# LED_backlight.net
KiCad netlist of a schematic drawn in Altium Designer
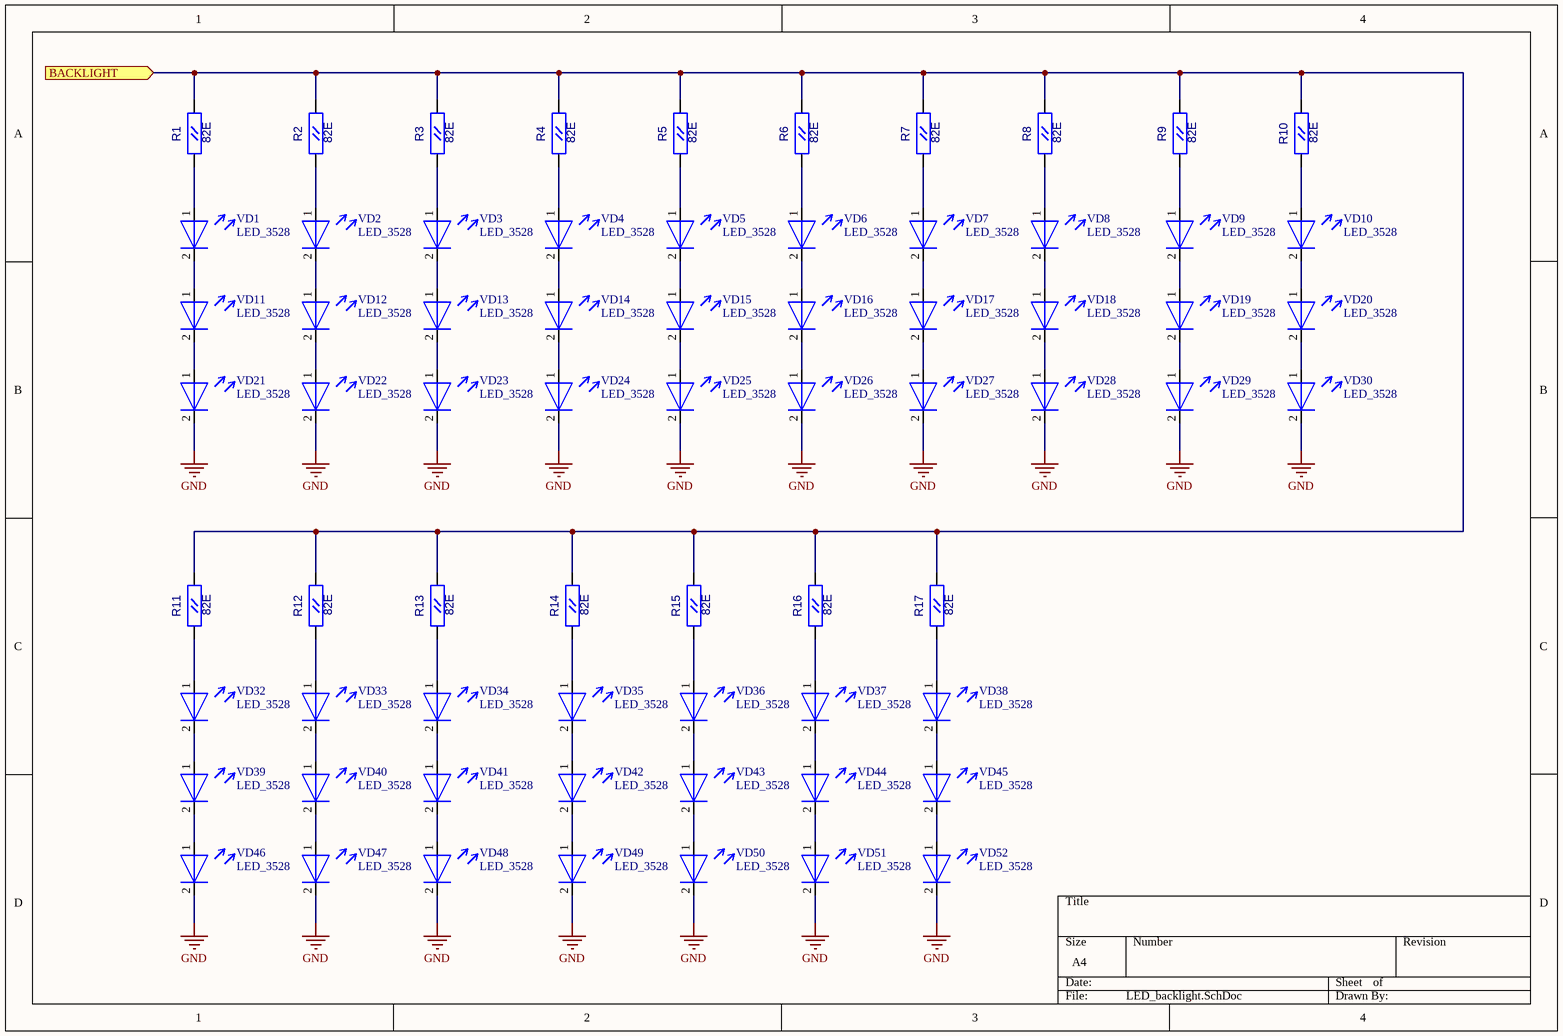
[diagram p0: LED_backlight.SchDoc]

(export (version "E")
  (design (tool "Eeschema 10.0.6"))
  (components
    (comp (ref "R1")
      (value "82E")
      (footprint "RC0805")
      (description "RC0805")
      (libsource (lib "gprs_modem_2") (part "RC0805"))
    )
    (comp (ref "R2")
      (value "82E")
      (footprint "RC0805")
      (description "RC0805")
      (libsource (lib "gprs_modem_2") (part "RC0805"))
    )
    (comp (ref "R3")
      (value "82E")
      (footprint "RC0805")
      (description "RC0805")
      (libsource (lib "gprs_modem_2") (part "RC0805"))
    )
    (comp (ref "R4")
      (value "82E")
      (footprint "RC0805")
      (description "RC0805")
      (libsource (lib "gprs_modem_2") (part "RC0805"))
    )
    (comp (ref "R5")
      (value "82E")
      (footprint "RC0805")
      (description "RC0805")
      (libsource (lib "gprs_modem_2") (part "RC0805"))
    )
    (comp (ref "R6")
      (value "82E")
      (footprint "RC0805")
      (description "RC0805")
      (libsource (lib "gprs_modem_2") (part "RC0805"))
    )
    (comp (ref "R7")
      (value "82E")
      (footprint "RC0805")
      (description "RC0805")
      (libsource (lib "gprs_modem_2") (part "RC0805"))
    )
    (comp (ref "R8")
      (value "82E")
      (footprint "RC0805")
      (description "RC0805")
      (libsource (lib "gprs_modem_2") (part "RC0805"))
    )
    (comp (ref "R9")
      (value "82E")
      (footprint "RC0805")
      (description "RC0805")
      (libsource (lib "gprs_modem_2") (part "RC0805"))
    )
    (comp (ref "R10")
      (value "82E")
      (footprint "RC0805")
      (description "RC0805")
      (libsource (lib "gprs_modem_2") (part "RC0805"))
    )
    (comp (ref "R11")
      (value "82E")
      (footprint "RC0805")
      (description "RC0805")
      (libsource (lib "gprs_modem_2") (part "RC0805"))
    )
    (comp (ref "R12")
      (value "82E")
      (footprint "RC0805")
      (description "RC0805")
      (libsource (lib "gprs_modem_2") (part "RC0805"))
    )
    (comp (ref "R13")
      (value "82E")
      (footprint "RC0805")
      (description "RC0805")
      (libsource (lib "gprs_modem_2") (part "RC0805"))
    )
    (comp (ref "R14")
      (value "82E")
      (footprint "RC0805")
      (description "RC0805")
      (libsource (lib "gprs_modem_2") (part "RC0805"))
    )
    (comp (ref "R15")
      (value "82E")
      (footprint "RC0805")
      (description "RC0805")
      (libsource (lib "gprs_modem_2") (part "RC0805"))
    )
    (comp (ref "R16")
      (value "82E")
      (footprint "RC0805")
      (description "RC0805")
      (libsource (lib "gprs_modem_2") (part "RC0805"))
    )
    (comp (ref "R17")
      (value "82E")
      (footprint "RC0805")
      (description "RC0805")
      (libsource (lib "gprs_modem_2") (part "RC0805"))
    )
    (comp (ref "VD1") (value "LED_3528") (footprint "3528LED") (libsource (lib "VHF") (part "3528LED")))
    (comp (ref "VD2") (value "LED_3528") (footprint "3528LED") (libsource (lib "VHF") (part "3528LED")))
    (comp (ref "VD3") (value "LED_3528") (footprint "3528LED") (libsource (lib "VHF") (part "3528LED")))
    (comp (ref "VD4") (value "LED_3528") (footprint "3528LED") (libsource (lib "VHF") (part "3528LED")))
    (comp (ref "VD5") (value "LED_3528") (footprint "3528LED") (libsource (lib "VHF") (part "3528LED")))
    (comp (ref "VD6") (value "LED_3528") (footprint "3528LED") (libsource (lib "VHF") (part "3528LED")))
    (comp (ref "VD7") (value "LED_3528") (footprint "3528LED") (libsource (lib "VHF") (part "3528LED")))
    (comp (ref "VD8") (value "LED_3528") (footprint "3528LED") (libsource (lib "VHF") (part "3528LED")))
    (comp (ref "VD9") (value "LED_3528") (footprint "3528LED") (libsource (lib "VHF") (part "3528LED")))
    (comp (ref "VD10") (value "LED_3528") (footprint "3528LED") (libsource (lib "VHF") (part "3528LED")))
    (comp (ref "VD11") (value "LED_3528") (footprint "3528LED") (libsource (lib "VHF") (part "3528LED")))
    (comp (ref "VD12") (value "LED_3528") (footprint "3528LED") (libsource (lib "VHF") (part "3528LED")))
    (comp (ref "VD13") (value "LED_3528") (footprint "3528LED") (libsource (lib "VHF") (part "3528LED")))
    (comp (ref "VD14") (value "LED_3528") (footprint "3528LED") (libsource (lib "VHF") (part "3528LED")))
    (comp (ref "VD15") (value "LED_3528") (footprint "3528LED") (libsource (lib "VHF") (part "3528LED")))
    (comp (ref "VD16") (value "LED_3528") (footprint "3528LED") (libsource (lib "VHF") (part "3528LED")))
    (comp (ref "VD17") (value "LED_3528") (footprint "3528LED") (libsource (lib "VHF") (part "3528LED")))
    (comp (ref "VD18") (value "LED_3528") (footprint "3528LED") (libsource (lib "VHF") (part "3528LED")))
    (comp (ref "VD19") (value "LED_3528") (footprint "3528LED") (libsource (lib "VHF") (part "3528LED")))
    (comp (ref "VD20") (value "LED_3528") (footprint "3528LED") (libsource (lib "VHF") (part "3528LED")))
    (comp (ref "VD21") (value "LED_3528") (footprint "3528LED") (libsource (lib "VHF") (part "3528LED")))
    (comp (ref "VD22") (value "LED_3528") (footprint "3528LED") (libsource (lib "VHF") (part "3528LED")))
    (comp (ref "VD23") (value "LED_3528") (footprint "3528LED") (libsource (lib "VHF") (part "3528LED")))
    (comp (ref "VD24") (value "LED_3528") (footprint "3528LED") (libsource (lib "VHF") (part "3528LED")))
    (comp (ref "VD25") (value "LED_3528") (footprint "3528LED") (libsource (lib "VHF") (part "3528LED")))
    (comp (ref "VD26") (value "LED_3528") (footprint "3528LED") (libsource (lib "VHF") (part "3528LED")))
    (comp (ref "VD27") (value "LED_3528") (footprint "3528LED") (libsource (lib "VHF") (part "3528LED")))
    (comp (ref "VD28") (value "LED_3528") (footprint "3528LED") (libsource (lib "VHF") (part "3528LED")))
    (comp (ref "VD29") (value "LED_3528") (footprint "3528LED") (libsource (lib "VHF") (part "3528LED")))
    (comp (ref "VD30") (value "LED_3528") (footprint "3528LED") (libsource (lib "VHF") (part "3528LED")))
    (comp (ref "VD32") (value "LED_3528") (footprint "3528LED") (libsource (lib "VHF") (part "3528LED")))
    (comp (ref "VD33") (value "LED_3528") (footprint "3528LED") (libsource (lib "VHF") (part "3528LED")))
    (comp (ref "VD34") (value "LED_3528") (footprint "3528LED") (libsource (lib "VHF") (part "3528LED")))
    (comp (ref "VD35") (value "LED_3528") (footprint "3528LED") (libsource (lib "VHF") (part "3528LED")))
    (comp (ref "VD36") (value "LED_3528") (footprint "3528LED") (libsource (lib "VHF") (part "3528LED")))
    (comp (ref "VD37") (value "LED_3528") (footprint "3528LED") (libsource (lib "VHF") (part "3528LED")))
    (comp (ref "VD38") (value "LED_3528") (footprint "3528LED") (libsource (lib "VHF") (part "3528LED")))
    (comp (ref "VD39") (value "LED_3528") (footprint "3528LED") (libsource (lib "VHF") (part "3528LED")))
    (comp (ref "VD40") (value "LED_3528") (footprint "3528LED") (libsource (lib "VHF") (part "3528LED")))
    (comp (ref "VD41") (value "LED_3528") (footprint "3528LED") (libsource (lib "VHF") (part "3528LED")))
    (comp (ref "VD42") (value "LED_3528") (footprint "3528LED") (libsource (lib "VHF") (part "3528LED")))
    (comp (ref "VD43") (value "LED_3528") (footprint "3528LED") (libsource (lib "VHF") (part "3528LED")))
    (comp (ref "VD44") (value "LED_3528") (footprint "3528LED") (libsource (lib "VHF") (part "3528LED")))
    (comp (ref "VD45") (value "LED_3528") (footprint "3528LED") (libsource (lib "VHF") (part "3528LED")))
    (comp (ref "VD46") (value "LED_3528") (footprint "3528LED") (libsource (lib "VHF") (part "3528LED")))
    (comp (ref "VD47") (value "LED_3528") (footprint "3528LED") (libsource (lib "VHF") (part "3528LED")))
    (comp (ref "VD48") (value "LED_3528") (footprint "3528LED") (libsource (lib "VHF") (part "3528LED")))
    (comp (ref "VD49") (value "LED_3528") (footprint "3528LED") (libsource (lib "VHF") (part "3528LED")))
    (comp (ref "VD50") (value "LED_3528") (footprint "3528LED") (libsource (lib "VHF") (part "3528LED")))
    (comp (ref "VD51") (value "LED_3528") (footprint "3528LED") (libsource (lib "VHF") (part "3528LED")))
    (comp (ref "VD52") (value "LED_3528") (footprint "3528LED") (libsource (lib "VHF") (part "3528LED")))
  )
  (nets
    (net (code "1") (name "/BACKLIGHT") (class "Default")
      (node (ref "R1") (pin "2") (pinfunction "B_2") (pintype "passive"))
      (node (ref "R10") (pin "2") (pinfunction "B_2") (pintype "passive"))
      (node (ref "R11") (pin "2") (pinfunction "B_2") (pintype "passive"))
      (node (ref "R12") (pin "2") (pinfunction "B_2") (pintype "passive"))
      (node (ref "R13") (pin "2") (pinfunction "B_2") (pintype "passive"))
      (node (ref "R14") (pin "2") (pinfunction "B_2") (pintype "passive"))
      (node (ref "R15") (pin "2") (pinfunction "B_2") (pintype "passive"))
      (node (ref "R16") (pin "2") (pinfunction "B_2") (pintype "passive"))
      (node (ref "R17") (pin "2") (pinfunction "B_2") (pintype "passive"))
      (node (ref "R2") (pin "2") (pinfunction "B_2") (pintype "passive"))
      (node (ref "R3") (pin "2") (pinfunction "B_2") (pintype "passive"))
      (node (ref "R4") (pin "2") (pinfunction "B_2") (pintype "passive"))
      (node (ref "R5") (pin "2") (pinfunction "B_2") (pintype "passive"))
      (node (ref "R6") (pin "2") (pinfunction "B_2") (pintype "passive"))
      (node (ref "R7") (pin "2") (pinfunction "B_2") (pintype "passive"))
      (node (ref "R8") (pin "2") (pinfunction "B_2") (pintype "passive"))
      (node (ref "R9") (pin "2") (pinfunction "B_2") (pintype "passive"))
    )
    (net (code "2") (name "GND") (class "Default")
      (node (ref "VD21") (pin "2") (pinfunction "K_2") (pintype "passive"))
      (node (ref "VD22") (pin "2") (pinfunction "K_2") (pintype "passive"))
      (node (ref "VD23") (pin "2") (pinfunction "K_2") (pintype "passive"))
      (node (ref "VD24") (pin "2") (pinfunction "K_2") (pintype "passive"))
      (node (ref "VD25") (pin "2") (pinfunction "K_2") (pintype "passive"))
      (node (ref "VD26") (pin "2") (pinfunction "K_2") (pintype "passive"))
      (node (ref "VD27") (pin "2") (pinfunction "K_2") (pintype "passive"))
      (node (ref "VD28") (pin "2") (pinfunction "K_2") (pintype "passive"))
      (node (ref "VD29") (pin "2") (pinfunction "K_2") (pintype "passive"))
      (node (ref "VD30") (pin "2") (pinfunction "K_2") (pintype "passive"))
      (node (ref "VD46") (pin "2") (pinfunction "K_2") (pintype "passive"))
      (node (ref "VD47") (pin "2") (pinfunction "K_2") (pintype "passive"))
      (node (ref "VD48") (pin "2") (pinfunction "K_2") (pintype "passive"))
      (node (ref "VD49") (pin "2") (pinfunction "K_2") (pintype "passive"))
      (node (ref "VD50") (pin "2") (pinfunction "K_2") (pintype "passive"))
      (node (ref "VD51") (pin "2") (pinfunction "K_2") (pintype "passive"))
      (node (ref "VD52") (pin "2") (pinfunction "K_2") (pintype "passive"))
    )
    (net (code "3") (name "Net-(R1-A)") (class "Default")
      (node (ref "R1") (pin "1") (pinfunction "A_1") (pintype "passive"))
      (node (ref "VD1") (pin "1") (pinfunction "A_1") (pintype "passive"))
    )
    (net (code "4") (name "Net-(R2-A)") (class "Default")
      (node (ref "R2") (pin "1") (pinfunction "A_1") (pintype "passive"))
      (node (ref "VD2") (pin "1") (pinfunction "A_1") (pintype "passive"))
    )
    (net (code "5") (name "Net-(R3-A)") (class "Default")
      (node (ref "R3") (pin "1") (pinfunction "A_1") (pintype "passive"))
      (node (ref "VD3") (pin "1") (pinfunction "A_1") (pintype "passive"))
    )
    (net (code "6") (name "Net-(R4-A)") (class "Default")
      (node (ref "R4") (pin "1") (pinfunction "A_1") (pintype "passive"))
      (node (ref "VD4") (pin "1") (pinfunction "A_1") (pintype "passive"))
    )
    (net (code "7") (name "Net-(R5-A)") (class "Default")
      (node (ref "R5") (pin "1") (pinfunction "A_1") (pintype "passive"))
      (node (ref "VD5") (pin "1") (pinfunction "A_1") (pintype "passive"))
    )
    (net (code "8") (name "Net-(R6-A)") (class "Default")
      (node (ref "R6") (pin "1") (pinfunction "A_1") (pintype "passive"))
      (node (ref "VD6") (pin "1") (pinfunction "A_1") (pintype "passive"))
    )
    (net (code "9") (name "Net-(R7-A)") (class "Default")
      (node (ref "R7") (pin "1") (pinfunction "A_1") (pintype "passive"))
      (node (ref "VD7") (pin "1") (pinfunction "A_1") (pintype "passive"))
    )
    (net (code "10") (name "Net-(R8-A)") (class "Default")
      (node (ref "R8") (pin "1") (pinfunction "A_1") (pintype "passive"))
      (node (ref "VD8") (pin "1") (pinfunction "A_1") (pintype "passive"))
    )
    (net (code "11") (name "Net-(R9-A)") (class "Default")
      (node (ref "R9") (pin "1") (pinfunction "A_1") (pintype "passive"))
      (node (ref "VD9") (pin "1") (pinfunction "A_1") (pintype "passive"))
    )
    (net (code "12") (name "Net-(R10-A)") (class "Default")
      (node (ref "R10") (pin "1") (pinfunction "A_1") (pintype "passive"))
      (node (ref "VD10") (pin "1") (pinfunction "A_1") (pintype "passive"))
    )
    (net (code "13") (name "Net-(R11-A)") (class "Default")
      (node (ref "R11") (pin "1") (pinfunction "A_1") (pintype "passive"))
      (node (ref "VD32") (pin "1") (pinfunction "A_1") (pintype "passive"))
    )
    (net (code "14") (name "Net-(R12-A)") (class "Default")
      (node (ref "R12") (pin "1") (pinfunction "A_1") (pintype "passive"))
      (node (ref "VD33") (pin "1") (pinfunction "A_1") (pintype "passive"))
    )
    (net (code "15") (name "Net-(R13-A)") (class "Default")
      (node (ref "R13") (pin "1") (pinfunction "A_1") (pintype "passive"))
      (node (ref "VD34") (pin "1") (pinfunction "A_1") (pintype "passive"))
    )
    (net (code "16") (name "Net-(R14-A)") (class "Default")
      (node (ref "R14") (pin "1") (pinfunction "A_1") (pintype "passive"))
      (node (ref "VD35") (pin "1") (pinfunction "A_1") (pintype "passive"))
    )
    (net (code "17") (name "Net-(R15-A)") (class "Default")
      (node (ref "R15") (pin "1") (pinfunction "A_1") (pintype "passive"))
      (node (ref "VD36") (pin "1") (pinfunction "A_1") (pintype "passive"))
    )
    (net (code "18") (name "Net-(R16-A)") (class "Default")
      (node (ref "R16") (pin "1") (pinfunction "A_1") (pintype "passive"))
      (node (ref "VD37") (pin "1") (pinfunction "A_1") (pintype "passive"))
    )
    (net (code "19") (name "Net-(R17-A)") (class "Default")
      (node (ref "R17") (pin "1") (pinfunction "A_1") (pintype "passive"))
      (node (ref "VD38") (pin "1") (pinfunction "A_1") (pintype "passive"))
    )
    (net (code "20") (name "Net-(VD1-K)") (class "Default")
      (node (ref "VD1") (pin "2") (pinfunction "K_2") (pintype "passive"))
      (node (ref "VD11") (pin "1") (pinfunction "A_1") (pintype "passive"))
    )
    (net (code "21") (name "Net-(VD10-K)") (class "Default")
      (node (ref "VD10") (pin "2") (pinfunction "K_2") (pintype "passive"))
      (node (ref "VD20") (pin "1") (pinfunction "A_1") (pintype "passive"))
    )
    (net (code "22") (name "Net-(VD11-K)") (class "Default")
      (node (ref "VD11") (pin "2") (pinfunction "K_2") (pintype "passive"))
      (node (ref "VD21") (pin "1") (pinfunction "A_1") (pintype "passive"))
    )
    (net (code "23") (name "Net-(VD12-A)") (class "Default")
      (node (ref "VD12") (pin "1") (pinfunction "A_1") (pintype "passive"))
      (node (ref "VD2") (pin "2") (pinfunction "K_2") (pintype "passive"))
    )
    (net (code "24") (name "Net-(VD12-K)") (class "Default")
      (node (ref "VD12") (pin "2") (pinfunction "K_2") (pintype "passive"))
      (node (ref "VD22") (pin "1") (pinfunction "A_1") (pintype "passive"))
    )
    (net (code "25") (name "Net-(VD13-A)") (class "Default")
      (node (ref "VD13") (pin "1") (pinfunction "A_1") (pintype "passive"))
      (node (ref "VD3") (pin "2") (pinfunction "K_2") (pintype "passive"))
    )
    (net (code "26") (name "Net-(VD13-K)") (class "Default")
      (node (ref "VD13") (pin "2") (pinfunction "K_2") (pintype "passive"))
      (node (ref "VD23") (pin "1") (pinfunction "A_1") (pintype "passive"))
    )
    (net (code "27") (name "Net-(VD14-A)") (class "Default")
      (node (ref "VD14") (pin "1") (pinfunction "A_1") (pintype "passive"))
      (node (ref "VD4") (pin "2") (pinfunction "K_2") (pintype "passive"))
    )
    (net (code "28") (name "Net-(VD14-K)") (class "Default")
      (node (ref "VD14") (pin "2") (pinfunction "K_2") (pintype "passive"))
      (node (ref "VD24") (pin "1") (pinfunction "A_1") (pintype "passive"))
    )
    (net (code "29") (name "Net-(VD15-A)") (class "Default")
      (node (ref "VD15") (pin "1") (pinfunction "A_1") (pintype "passive"))
      (node (ref "VD5") (pin "2") (pinfunction "K_2") (pintype "passive"))
    )
    (net (code "30") (name "Net-(VD15-K)") (class "Default")
      (node (ref "VD15") (pin "2") (pinfunction "K_2") (pintype "passive"))
      (node (ref "VD25") (pin "1") (pinfunction "A_1") (pintype "passive"))
    )
    (net (code "31") (name "Net-(VD16-A)") (class "Default")
      (node (ref "VD16") (pin "1") (pinfunction "A_1") (pintype "passive"))
      (node (ref "VD6") (pin "2") (pinfunction "K_2") (pintype "passive"))
    )
    (net (code "32") (name "Net-(VD16-K)") (class "Default")
      (node (ref "VD16") (pin "2") (pinfunction "K_2") (pintype "passive"))
      (node (ref "VD26") (pin "1") (pinfunction "A_1") (pintype "passive"))
    )
    (net (code "33") (name "Net-(VD17-A)") (class "Default")
      (node (ref "VD17") (pin "1") (pinfunction "A_1") (pintype "passive"))
      (node (ref "VD7") (pin "2") (pinfunction "K_2") (pintype "passive"))
    )
    (net (code "34") (name "Net-(VD17-K)") (class "Default")
      (node (ref "VD17") (pin "2") (pinfunction "K_2") (pintype "passive"))
      (node (ref "VD27") (pin "1") (pinfunction "A_1") (pintype "passive"))
    )
    (net (code "35") (name "Net-(VD18-A)") (class "Default")
      (node (ref "VD18") (pin "1") (pinfunction "A_1") (pintype "passive"))
      (node (ref "VD8") (pin "2") (pinfunction "K_2") (pintype "passive"))
    )
    (net (code "36") (name "Net-(VD18-K)") (class "Default")
      (node (ref "VD18") (pin "2") (pinfunction "K_2") (pintype "passive"))
      (node (ref "VD28") (pin "1") (pinfunction "A_1") (pintype "passive"))
    )
    (net (code "37") (name "Net-(VD19-A)") (class "Default")
      (node (ref "VD19") (pin "1") (pinfunction "A_1") (pintype "passive"))
      (node (ref "VD9") (pin "2") (pinfunction "K_2") (pintype "passive"))
    )
    (net (code "38") (name "Net-(VD19-K)") (class "Default")
      (node (ref "VD19") (pin "2") (pinfunction "K_2") (pintype "passive"))
      (node (ref "VD29") (pin "1") (pinfunction "A_1") (pintype "passive"))
    )
    (net (code "39") (name "Net-(VD20-K)") (class "Default")
      (node (ref "VD20") (pin "2") (pinfunction "K_2") (pintype "passive"))
      (node (ref "VD30") (pin "1") (pinfunction "A_1") (pintype "passive"))
    )
    (net (code "40") (name "Net-(VD32-K)") (class "Default")
      (node (ref "VD32") (pin "2") (pinfunction "K_2") (pintype "passive"))
      (node (ref "VD39") (pin "1") (pinfunction "A_1") (pintype "passive"))
    )
    (net (code "41") (name "Net-(VD33-K)") (class "Default")
      (node (ref "VD33") (pin "2") (pinfunction "K_2") (pintype "passive"))
      (node (ref "VD40") (pin "1") (pinfunction "A_1") (pintype "passive"))
    )
    (net (code "42") (name "Net-(VD34-K)") (class "Default")
      (node (ref "VD34") (pin "2") (pinfunction "K_2") (pintype "passive"))
      (node (ref "VD41") (pin "1") (pinfunction "A_1") (pintype "passive"))
    )
    (net (code "43") (name "Net-(VD35-K)") (class "Default")
      (node (ref "VD35") (pin "2") (pinfunction "K_2") (pintype "passive"))
      (node (ref "VD42") (pin "1") (pinfunction "A_1") (pintype "passive"))
    )
    (net (code "44") (name "Net-(VD36-K)") (class "Default")
      (node (ref "VD36") (pin "2") (pinfunction "K_2") (pintype "passive"))
      (node (ref "VD43") (pin "1") (pinfunction "A_1") (pintype "passive"))
    )
    (net (code "45") (name "Net-(VD37-K)") (class "Default")
      (node (ref "VD37") (pin "2") (pinfunction "K_2") (pintype "passive"))
      (node (ref "VD44") (pin "1") (pinfunction "A_1") (pintype "passive"))
    )
    (net (code "46") (name "Net-(VD38-K)") (class "Default")
      (node (ref "VD38") (pin "2") (pinfunction "K_2") (pintype "passive"))
      (node (ref "VD45") (pin "1") (pinfunction "A_1") (pintype "passive"))
    )
    (net (code "47") (name "Net-(VD39-K)") (class "Default")
      (node (ref "VD39") (pin "2") (pinfunction "K_2") (pintype "passive"))
      (node (ref "VD46") (pin "1") (pinfunction "A_1") (pintype "passive"))
    )
    (net (code "48") (name "Net-(VD40-K)") (class "Default")
      (node (ref "VD40") (pin "2") (pinfunction "K_2") (pintype "passive"))
      (node (ref "VD47") (pin "1") (pinfunction "A_1") (pintype "passive"))
    )
    (net (code "49") (name "Net-(VD41-K)") (class "Default")
      (node (ref "VD41") (pin "2") (pinfunction "K_2") (pintype "passive"))
      (node (ref "VD48") (pin "1") (pinfunction "A_1") (pintype "passive"))
    )
    (net (code "50") (name "Net-(VD42-K)") (class "Default")
      (node (ref "VD42") (pin "2") (pinfunction "K_2") (pintype "passive"))
      (node (ref "VD49") (pin "1") (pinfunction "A_1") (pintype "passive"))
    )
    (net (code "51") (name "Net-(VD43-K)") (class "Default")
      (node (ref "VD43") (pin "2") (pinfunction "K_2") (pintype "passive"))
      (node (ref "VD50") (pin "1") (pinfunction "A_1") (pintype "passive"))
    )
    (net (code "52") (name "Net-(VD44-K)") (class "Default")
      (node (ref "VD44") (pin "2") (pinfunction "K_2") (pintype "passive"))
      (node (ref "VD51") (pin "1") (pinfunction "A_1") (pintype "passive"))
    )
    (net (code "53") (name "Net-(VD45-K)") (class "Default")
      (node (ref "VD45") (pin "2") (pinfunction "K_2") (pintype "passive"))
      (node (ref "VD52") (pin "1") (pinfunction "A_1") (pintype "passive"))
    )
  )
)
